# RoBeast_Positional_Feedback.net
KiCad netlist of a schematic drawn in Altium Designer
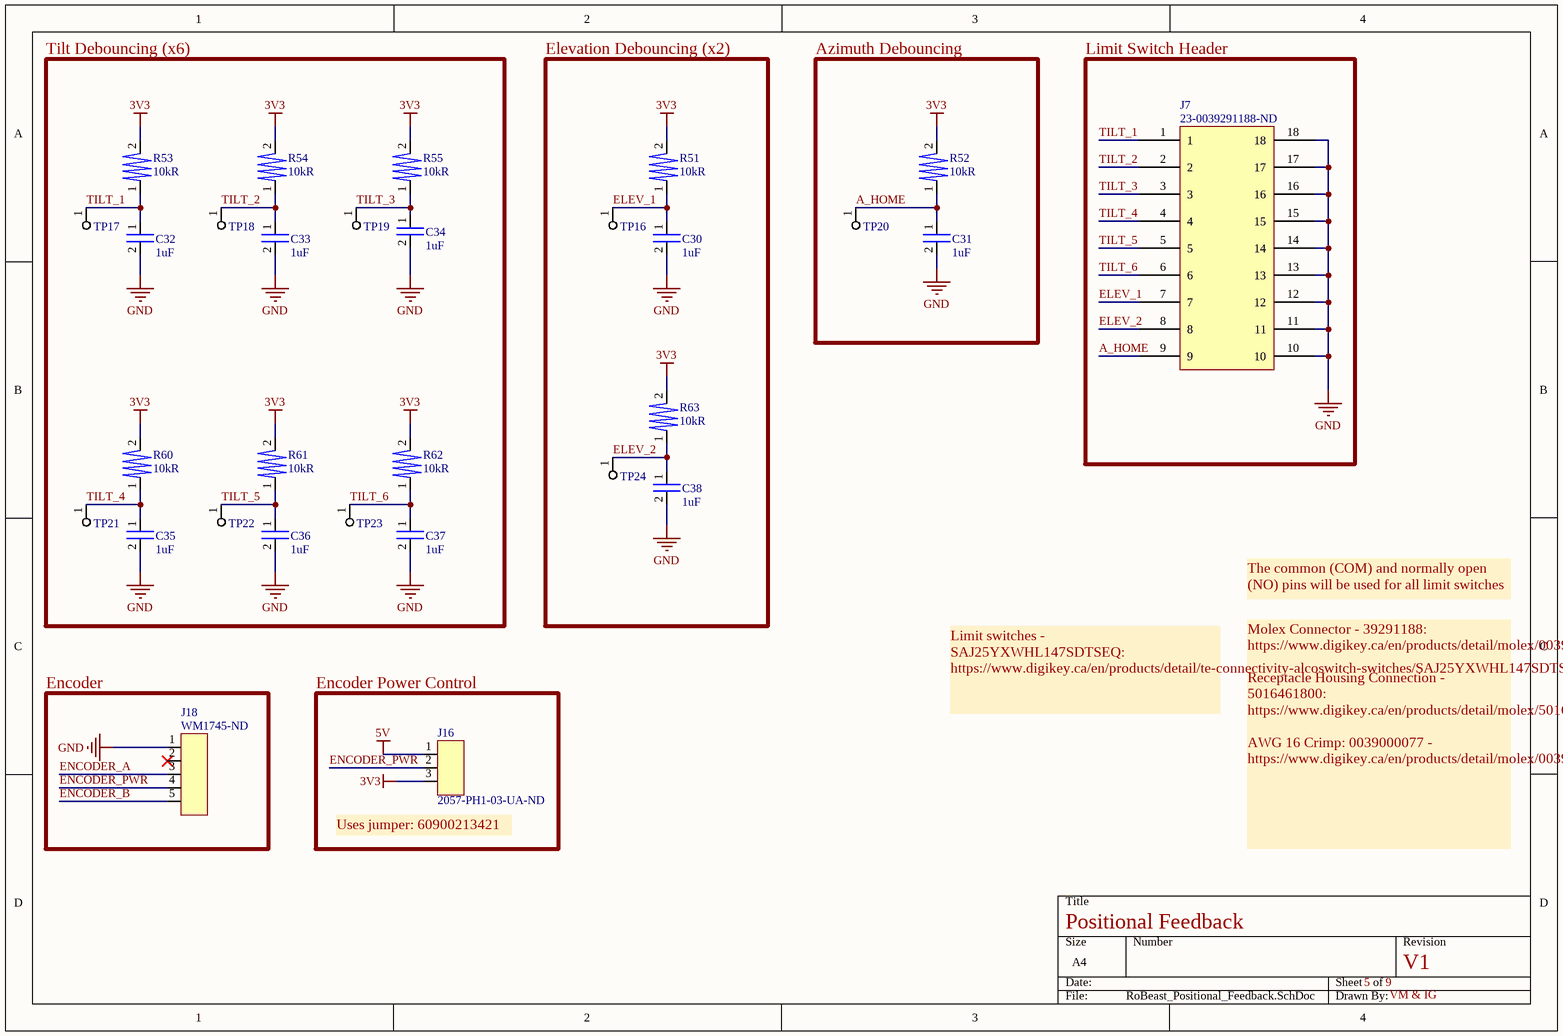
[diagram p0: RoBeast_Positional_Feedback.SchDoc]

(export (version "E")
  (design (tool "Eeschema 10.0.6"))
  (components
    (comp (ref "C30")
      (value "1uF")
      (footprint "0805")
      (fields
        (field (name "MANUFACTURER") "Yageo")
        (field (name "MANUFACTURER PART NUMBER") "CC0805JKX7R9BB105")
      )
      (libsource (lib "RoBeast_Schematic_Library") (part "CC0805JKX7R9BB105"))
    )
    (comp (ref "C31")
      (value "1uF")
      (footprint "0805")
      (fields
        (field (name "MANUFACTURER") "Yageo")
        (field (name "MANUFACTURER PART NUMBER") "CC0805JKX7R9BB105")
      )
      (libsource (lib "RoBeast_Schematic_Library") (part "CC0805JKX7R9BB105"))
    )
    (comp (ref "C32")
      (value "1uF")
      (footprint "0805")
      (fields
        (field (name "MANUFACTURER") "Yageo")
        (field (name "MANUFACTURER PART NUMBER") "CC0805JKX7R9BB105")
      )
      (libsource (lib "RoBeast_Schematic_Library") (part "CC0805JKX7R9BB105"))
    )
    (comp (ref "C33")
      (value "1uF")
      (footprint "0805")
      (fields
        (field (name "MANUFACTURER") "Yageo")
        (field (name "MANUFACTURER PART NUMBER") "CC0805JKX7R9BB105")
      )
      (libsource (lib "RoBeast_Schematic_Library") (part "CC0805JKX7R9BB105"))
    )
    (comp (ref "C34")
      (value "1uF")
      (footprint "0805")
      (fields
        (field (name "MANUFACTURER") "Yageo")
        (field (name "MANUFACTURER PART NUMBER") "CC0805JKX7R9BB105")
      )
      (libsource (lib "RoBeast_Schematic_Library") (part "CC0805JKX7R9BB105"))
    )
    (comp (ref "C35")
      (value "1uF")
      (footprint "0805")
      (fields
        (field (name "MANUFACTURER") "Yageo")
        (field (name "MANUFACTURER PART NUMBER") "CC0805JKX7R9BB105")
      )
      (libsource (lib "RoBeast_Schematic_Library") (part "CC0805JKX7R9BB105"))
    )
    (comp (ref "C36")
      (value "1uF")
      (footprint "0805")
      (fields
        (field (name "MANUFACTURER") "Yageo")
        (field (name "MANUFACTURER PART NUMBER") "CC0805JKX7R9BB105")
      )
      (libsource (lib "RoBeast_Schematic_Library") (part "CC0805JKX7R9BB105"))
    )
    (comp (ref "C37")
      (value "1uF")
      (footprint "0805")
      (fields
        (field (name "MANUFACTURER") "Yageo")
        (field (name "MANUFACTURER PART NUMBER") "CC0805JKX7R9BB105")
      )
      (libsource (lib "RoBeast_Schematic_Library") (part "CC0805JKX7R9BB105"))
    )
    (comp (ref "C38")
      (value "1uF")
      (footprint "0805")
      (fields
        (field (name "MANUFACTURER") "Yageo")
        (field (name "MANUFACTURER PART NUMBER") "CC0805JKX7R9BB105")
      )
      (libsource (lib "RoBeast_Schematic_Library") (part "CC0805JKX7R9BB105"))
    )
    (comp (ref "J7")
      (value "18 Pin Connector")
      (footprint "0039291188")
      (description "Rectangular Power Connector, 18 Contact(s), Male, Solder Terminal, Receptacle")
      (fields
        (field (name "MANUFACTURER") "Molex")
        (field (name "MANUFACTURER PART NUMBER") "39-29-1188")
        (field (name "SUPPLIER PART NUMBER 1") "23-0039291188-ND")
      )
      (libsource (lib "RoBeast_Schematic_Library") (part "0039291188"))
    )
    (comp (ref "J16")
      (value "3 Pin Connector")
      (footprint "PH1-03-UA")
      (description "Conn Unshrouded Header HDR 3 POS 2.54mm Solder ST Thru-Hole Bag")
      (fields
        (field (name "MANUFACTURER") "Adam Equipment")
        (field (name "MANUFACTURER PART NUMBER") "PH1-03-UA")
        (field (name "SUPPLIER PART NUMBER 1") "2057-PH1-03-UA-ND")
      )
      (libsource (lib "RoBeast_Schematic_Library") (part "PH1-03-UA"))
    )
    (comp (ref "J18")
      (value "5 Pin Male Connector")
      (footprint "0530480510")
      (fields
        (field (name "MANUFACTURER") "Molex")
        (field (name "MANUFACTURER PART NUMBER") "53048-0510")
        (field (name "SUPPLIER PART NUMBER") "WM1745-ND")
      )
      (libsource (lib "RoBeast_Schematic_Library") (part "0530480510"))
    )
    (comp (ref "R51")
      (value "10kR")
      (footprint "0805")
      (fields
        (field (name "MANUFACTURER") "Stackpole Electronics")
        (field (name "MANUFACTURER PART NUMBER") "RMCF0805FT10K0")
        (field (name "TOLERANCE") "1%")
      )
      (libsource (lib "RoBeast_Schematic_Library") (part "RMCF0805FT10K0"))
    )
    (comp (ref "R52")
      (value "10kR")
      (footprint "0805")
      (fields
        (field (name "MANUFACTURER") "Stackpole Electronics")
        (field (name "MANUFACTURER PART NUMBER") "RMCF0805FT10K0")
        (field (name "TOLERANCE") "1%")
      )
      (libsource (lib "RoBeast_Schematic_Library") (part "RMCF0805FT10K0"))
    )
    (comp (ref "R53")
      (value "10kR")
      (footprint "0805")
      (fields
        (field (name "MANUFACTURER") "Stackpole Electronics")
        (field (name "MANUFACTURER PART NUMBER") "RMCF0805FT10K0")
        (field (name "TOLERANCE") "1%")
      )
      (libsource (lib "RoBeast_Schematic_Library") (part "RMCF0805FT10K0"))
    )
    (comp (ref "R54")
      (value "10kR")
      (footprint "0805")
      (fields
        (field (name "MANUFACTURER") "Stackpole Electronics")
        (field (name "MANUFACTURER PART NUMBER") "RMCF0805FT10K0")
        (field (name "TOLERANCE") "1%")
      )
      (libsource (lib "RoBeast_Schematic_Library") (part "RMCF0805FT10K0"))
    )
    (comp (ref "R55")
      (value "10kR")
      (footprint "0805")
      (fields
        (field (name "MANUFACTURER") "Stackpole Electronics")
        (field (name "MANUFACTURER PART NUMBER") "RMCF0805FT10K0")
        (field (name "TOLERANCE") "1%")
      )
      (libsource (lib "RoBeast_Schematic_Library") (part "RMCF0805FT10K0"))
    )
    (comp (ref "R60")
      (value "10kR")
      (footprint "0805")
      (fields
        (field (name "MANUFACTURER") "Stackpole Electronics")
        (field (name "MANUFACTURER PART NUMBER") "RMCF0805FT10K0")
        (field (name "TOLERANCE") "1%")
      )
      (libsource (lib "RoBeast_Schematic_Library") (part "RMCF0805FT10K0"))
    )
    (comp (ref "R61")
      (value "10kR")
      (footprint "0805")
      (fields
        (field (name "MANUFACTURER") "Stackpole Electronics")
        (field (name "MANUFACTURER PART NUMBER") "RMCF0805FT10K0")
        (field (name "TOLERANCE") "1%")
      )
      (libsource (lib "RoBeast_Schematic_Library") (part "RMCF0805FT10K0"))
    )
    (comp (ref "R62")
      (value "10kR")
      (footprint "0805")
      (fields
        (field (name "MANUFACTURER") "Stackpole Electronics")
        (field (name "MANUFACTURER PART NUMBER") "RMCF0805FT10K0")
        (field (name "TOLERANCE") "1%")
      )
      (libsource (lib "RoBeast_Schematic_Library") (part "RMCF0805FT10K0"))
    )
    (comp (ref "R63")
      (value "10kR")
      (footprint "0805")
      (fields
        (field (name "MANUFACTURER") "Stackpole Electronics")
        (field (name "MANUFACTURER PART NUMBER") "RMCF0805FT10K0")
        (field (name "TOLERANCE") "1%")
      )
      (libsource (lib "RoBeast_Schematic_Library") (part "RMCF0805FT10K0"))
    )
    (comp (ref "TP16")
      (value "Test Point")
      (footprint "RCWCTE")
      (description "Testing/Accessories")
      (fields (field (name "MANUFACTURER") "KOA Speer") (field (name "MANUFACTURER PART NUMBER") "RCWCTE"))
      (libsource (lib "RoBeast_Schematic_Library") (part "RCWCTE"))
    )
    (comp (ref "TP17")
      (value "Test Point")
      (footprint "RCWCTE")
      (description "Testing/Accessories")
      (fields (field (name "MANUFACTURER") "KOA Speer") (field (name "MANUFACTURER PART NUMBER") "RCWCTE"))
      (libsource (lib "RoBeast_Schematic_Library") (part "RCWCTE"))
    )
    (comp (ref "TP18")
      (value "Test Point")
      (footprint "RCWCTE")
      (description "Testing/Accessories")
      (fields (field (name "MANUFACTURER") "KOA Speer") (field (name "MANUFACTURER PART NUMBER") "RCWCTE"))
      (libsource (lib "RoBeast_Schematic_Library") (part "RCWCTE"))
    )
    (comp (ref "TP19")
      (value "Test Point")
      (footprint "RCWCTE")
      (description "Testing/Accessories")
      (fields (field (name "MANUFACTURER") "KOA Speer") (field (name "MANUFACTURER PART NUMBER") "RCWCTE"))
      (libsource (lib "RoBeast_Schematic_Library") (part "RCWCTE"))
    )
    (comp (ref "TP20")
      (value "Test Point")
      (footprint "RCWCTE")
      (description "Testing/Accessories")
      (fields (field (name "MANUFACTURER") "KOA Speer") (field (name "MANUFACTURER PART NUMBER") "RCWCTE"))
      (libsource (lib "RoBeast_Schematic_Library") (part "RCWCTE"))
    )
    (comp (ref "TP21")
      (value "Test Point")
      (footprint "RCWCTE")
      (description "Testing/Accessories")
      (fields (field (name "MANUFACTURER") "KOA Speer") (field (name "MANUFACTURER PART NUMBER") "RCWCTE"))
      (libsource (lib "RoBeast_Schematic_Library") (part "RCWCTE"))
    )
    (comp (ref "TP22")
      (value "Test Point")
      (footprint "RCWCTE")
      (description "Testing/Accessories")
      (fields (field (name "MANUFACTURER") "KOA Speer") (field (name "MANUFACTURER PART NUMBER") "RCWCTE"))
      (libsource (lib "RoBeast_Schematic_Library") (part "RCWCTE"))
    )
    (comp (ref "TP23")
      (value "Test Point")
      (footprint "RCWCTE")
      (description "Testing/Accessories")
      (fields (field (name "MANUFACTURER") "KOA Speer") (field (name "MANUFACTURER PART NUMBER") "RCWCTE"))
      (libsource (lib "RoBeast_Schematic_Library") (part "RCWCTE"))
    )
    (comp (ref "TP24")
      (value "Test Point")
      (footprint "RCWCTE")
      (description "Testing/Accessories")
      (fields (field (name "MANUFACTURER") "KOA Speer") (field (name "MANUFACTURER PART NUMBER") "RCWCTE"))
      (libsource (lib "RoBeast_Schematic_Library") (part "RCWCTE"))
    )
  )
  (nets
    (net (code "1") (name "/A_HOME") (class "Default")
      (node (ref "C31") (pin "1") (pinfunction "1_1") (pintype "passive"))
      (node (ref "J7") (pin "9") (pinfunction "9_9") (pintype "passive"))
      (node (ref "R52") (pin "1") (pinfunction "1_1") (pintype "passive"))
      (node (ref "TP20") (pin "1") (pinfunction "1_1") (pintype "passive"))
    )
    (net (code "2") (name "/ELEV_1") (class "Default")
      (node (ref "C30") (pin "1") (pinfunction "1_1") (pintype "passive"))
      (node (ref "J7") (pin "7") (pinfunction "7_7") (pintype "passive"))
      (node (ref "R51") (pin "1") (pinfunction "1_1") (pintype "passive"))
      (node (ref "TP16") (pin "1") (pinfunction "1_1") (pintype "passive"))
    )
    (net (code "3") (name "/ELEV_2") (class "Default")
      (node (ref "C38") (pin "1") (pinfunction "1_1") (pintype "passive"))
      (node (ref "J7") (pin "8") (pinfunction "8_8") (pintype "passive"))
      (node (ref "R63") (pin "1") (pinfunction "1_1") (pintype "passive"))
      (node (ref "TP24") (pin "1") (pinfunction "1_1") (pintype "passive"))
    )
    (net (code "4") (name "/ENCODER_A") (class "Default")
      (node (ref "J18") (pin "3") (pinfunction "3_3") (pintype "passive"))
    )
    (net (code "5") (name "/ENCODER_B") (class "Default")
      (node (ref "J18") (pin "5") (pinfunction "5_5") (pintype "passive"))
    )
    (net (code "6") (name "/ENCODER_PWR") (class "Default")
      (node (ref "J16") (pin "2") (pinfunction "2_2") (pintype "passive"))
      (node (ref "J18") (pin "4") (pinfunction "4_4") (pintype "passive"))
    )
    (net (code "7") (name "/TILT_1") (class "Default")
      (node (ref "C32") (pin "1") (pinfunction "1_1") (pintype "passive"))
      (node (ref "J7") (pin "1") (pinfunction "1_1") (pintype "passive"))
      (node (ref "R53") (pin "1") (pinfunction "1_1") (pintype "passive"))
      (node (ref "TP17") (pin "1") (pinfunction "1_1") (pintype "passive"))
    )
    (net (code "8") (name "/TILT_2") (class "Default")
      (node (ref "C33") (pin "1") (pinfunction "1_1") (pintype "passive"))
      (node (ref "J7") (pin "2") (pinfunction "2_2") (pintype "passive"))
      (node (ref "R54") (pin "1") (pinfunction "1_1") (pintype "passive"))
      (node (ref "TP18") (pin "1") (pinfunction "1_1") (pintype "passive"))
    )
    (net (code "9") (name "/TILT_3") (class "Default")
      (node (ref "C34") (pin "1") (pinfunction "1_1") (pintype "passive"))
      (node (ref "J7") (pin "3") (pinfunction "3_3") (pintype "passive"))
      (node (ref "R55") (pin "1") (pinfunction "1_1") (pintype "passive"))
      (node (ref "TP19") (pin "1") (pinfunction "1_1") (pintype "passive"))
    )
    (net (code "10") (name "/TILT_4") (class "Default")
      (node (ref "C35") (pin "1") (pinfunction "1_1") (pintype "passive"))
      (node (ref "J7") (pin "4") (pinfunction "4_4") (pintype "passive"))
      (node (ref "R60") (pin "1") (pinfunction "1_1") (pintype "passive"))
      (node (ref "TP21") (pin "1") (pinfunction "1_1") (pintype "passive"))
    )
    (net (code "11") (name "/TILT_5") (class "Default")
      (node (ref "C36") (pin "1") (pinfunction "1_1") (pintype "passive"))
      (node (ref "J7") (pin "5") (pinfunction "5_5") (pintype "passive"))
      (node (ref "R61") (pin "1") (pinfunction "1_1") (pintype "passive"))
      (node (ref "TP22") (pin "1") (pinfunction "1_1") (pintype "passive"))
    )
    (net (code "12") (name "/TILT_6") (class "Default")
      (node (ref "C37") (pin "1") (pinfunction "1_1") (pintype "passive"))
      (node (ref "J7") (pin "6") (pinfunction "6_6") (pintype "passive"))
      (node (ref "R62") (pin "1") (pinfunction "1_1") (pintype "passive"))
      (node (ref "TP23") (pin "1") (pinfunction "1_1") (pintype "passive"))
    )
    (net (code "13") (name "3V3") (class "Default")
      (node (ref "J16") (pin "3") (pinfunction "3_3") (pintype "passive"))
      (node (ref "R51") (pin "2") (pinfunction "2_2") (pintype "passive"))
      (node (ref "R52") (pin "2") (pinfunction "2_2") (pintype "passive"))
      (node (ref "R53") (pin "2") (pinfunction "2_2") (pintype "passive"))
      (node (ref "R54") (pin "2") (pinfunction "2_2") (pintype "passive"))
      (node (ref "R55") (pin "2") (pinfunction "2_2") (pintype "passive"))
      (node (ref "R60") (pin "2") (pinfunction "2_2") (pintype "passive"))
      (node (ref "R61") (pin "2") (pinfunction "2_2") (pintype "passive"))
      (node (ref "R62") (pin "2") (pinfunction "2_2") (pintype "passive"))
      (node (ref "R63") (pin "2") (pinfunction "2_2") (pintype "passive"))
    )
    (net (code "14") (name "5V") (class "Default")
      (node (ref "J16") (pin "1") (pinfunction "1_1") (pintype "passive"))
    )
    (net (code "15") (name "GND") (class "Default")
      (node (ref "C30") (pin "2") (pinfunction "2_2") (pintype "passive"))
      (node (ref "C31") (pin "2") (pinfunction "2_2") (pintype "passive"))
      (node (ref "C32") (pin "2") (pinfunction "2_2") (pintype "passive"))
      (node (ref "C33") (pin "2") (pinfunction "2_2") (pintype "passive"))
      (node (ref "C34") (pin "2") (pinfunction "2_2") (pintype "passive"))
      (node (ref "C35") (pin "2") (pinfunction "2_2") (pintype "passive"))
      (node (ref "C36") (pin "2") (pinfunction "2_2") (pintype "passive"))
      (node (ref "C37") (pin "2") (pinfunction "2_2") (pintype "passive"))
      (node (ref "C38") (pin "2") (pinfunction "2_2") (pintype "passive"))
      (node (ref "J18") (pin "1") (pinfunction "1_1") (pintype "passive"))
      (node (ref "J7") (pin "10") (pinfunction "10_10") (pintype "passive"))
      (node (ref "J7") (pin "11") (pinfunction "11_11") (pintype "passive"))
      (node (ref "J7") (pin "12") (pinfunction "12_12") (pintype "passive"))
      (node (ref "J7") (pin "13") (pinfunction "13_13") (pintype "passive"))
      (node (ref "J7") (pin "14") (pinfunction "14_14") (pintype "passive"))
      (node (ref "J7") (pin "15") (pinfunction "15_15") (pintype "passive"))
      (node (ref "J7") (pin "16") (pinfunction "16_16") (pintype "passive"))
      (node (ref "J7") (pin "17") (pinfunction "17_17") (pintype "passive"))
      (node (ref "J7") (pin "18") (pinfunction "18_18") (pintype "passive"))
    )
    (net (code "16") (name "unconnected-(J18-Pad2)") (class "Default")
      (node (ref "J18") (pin "2") (pinfunction "2_2") (pintype "passive+no_connect"))
    )
  )
)
